# Contatore_a_relay_4bit_-_Product.net
KiCad netlist of a schematic drawn in EAGLE
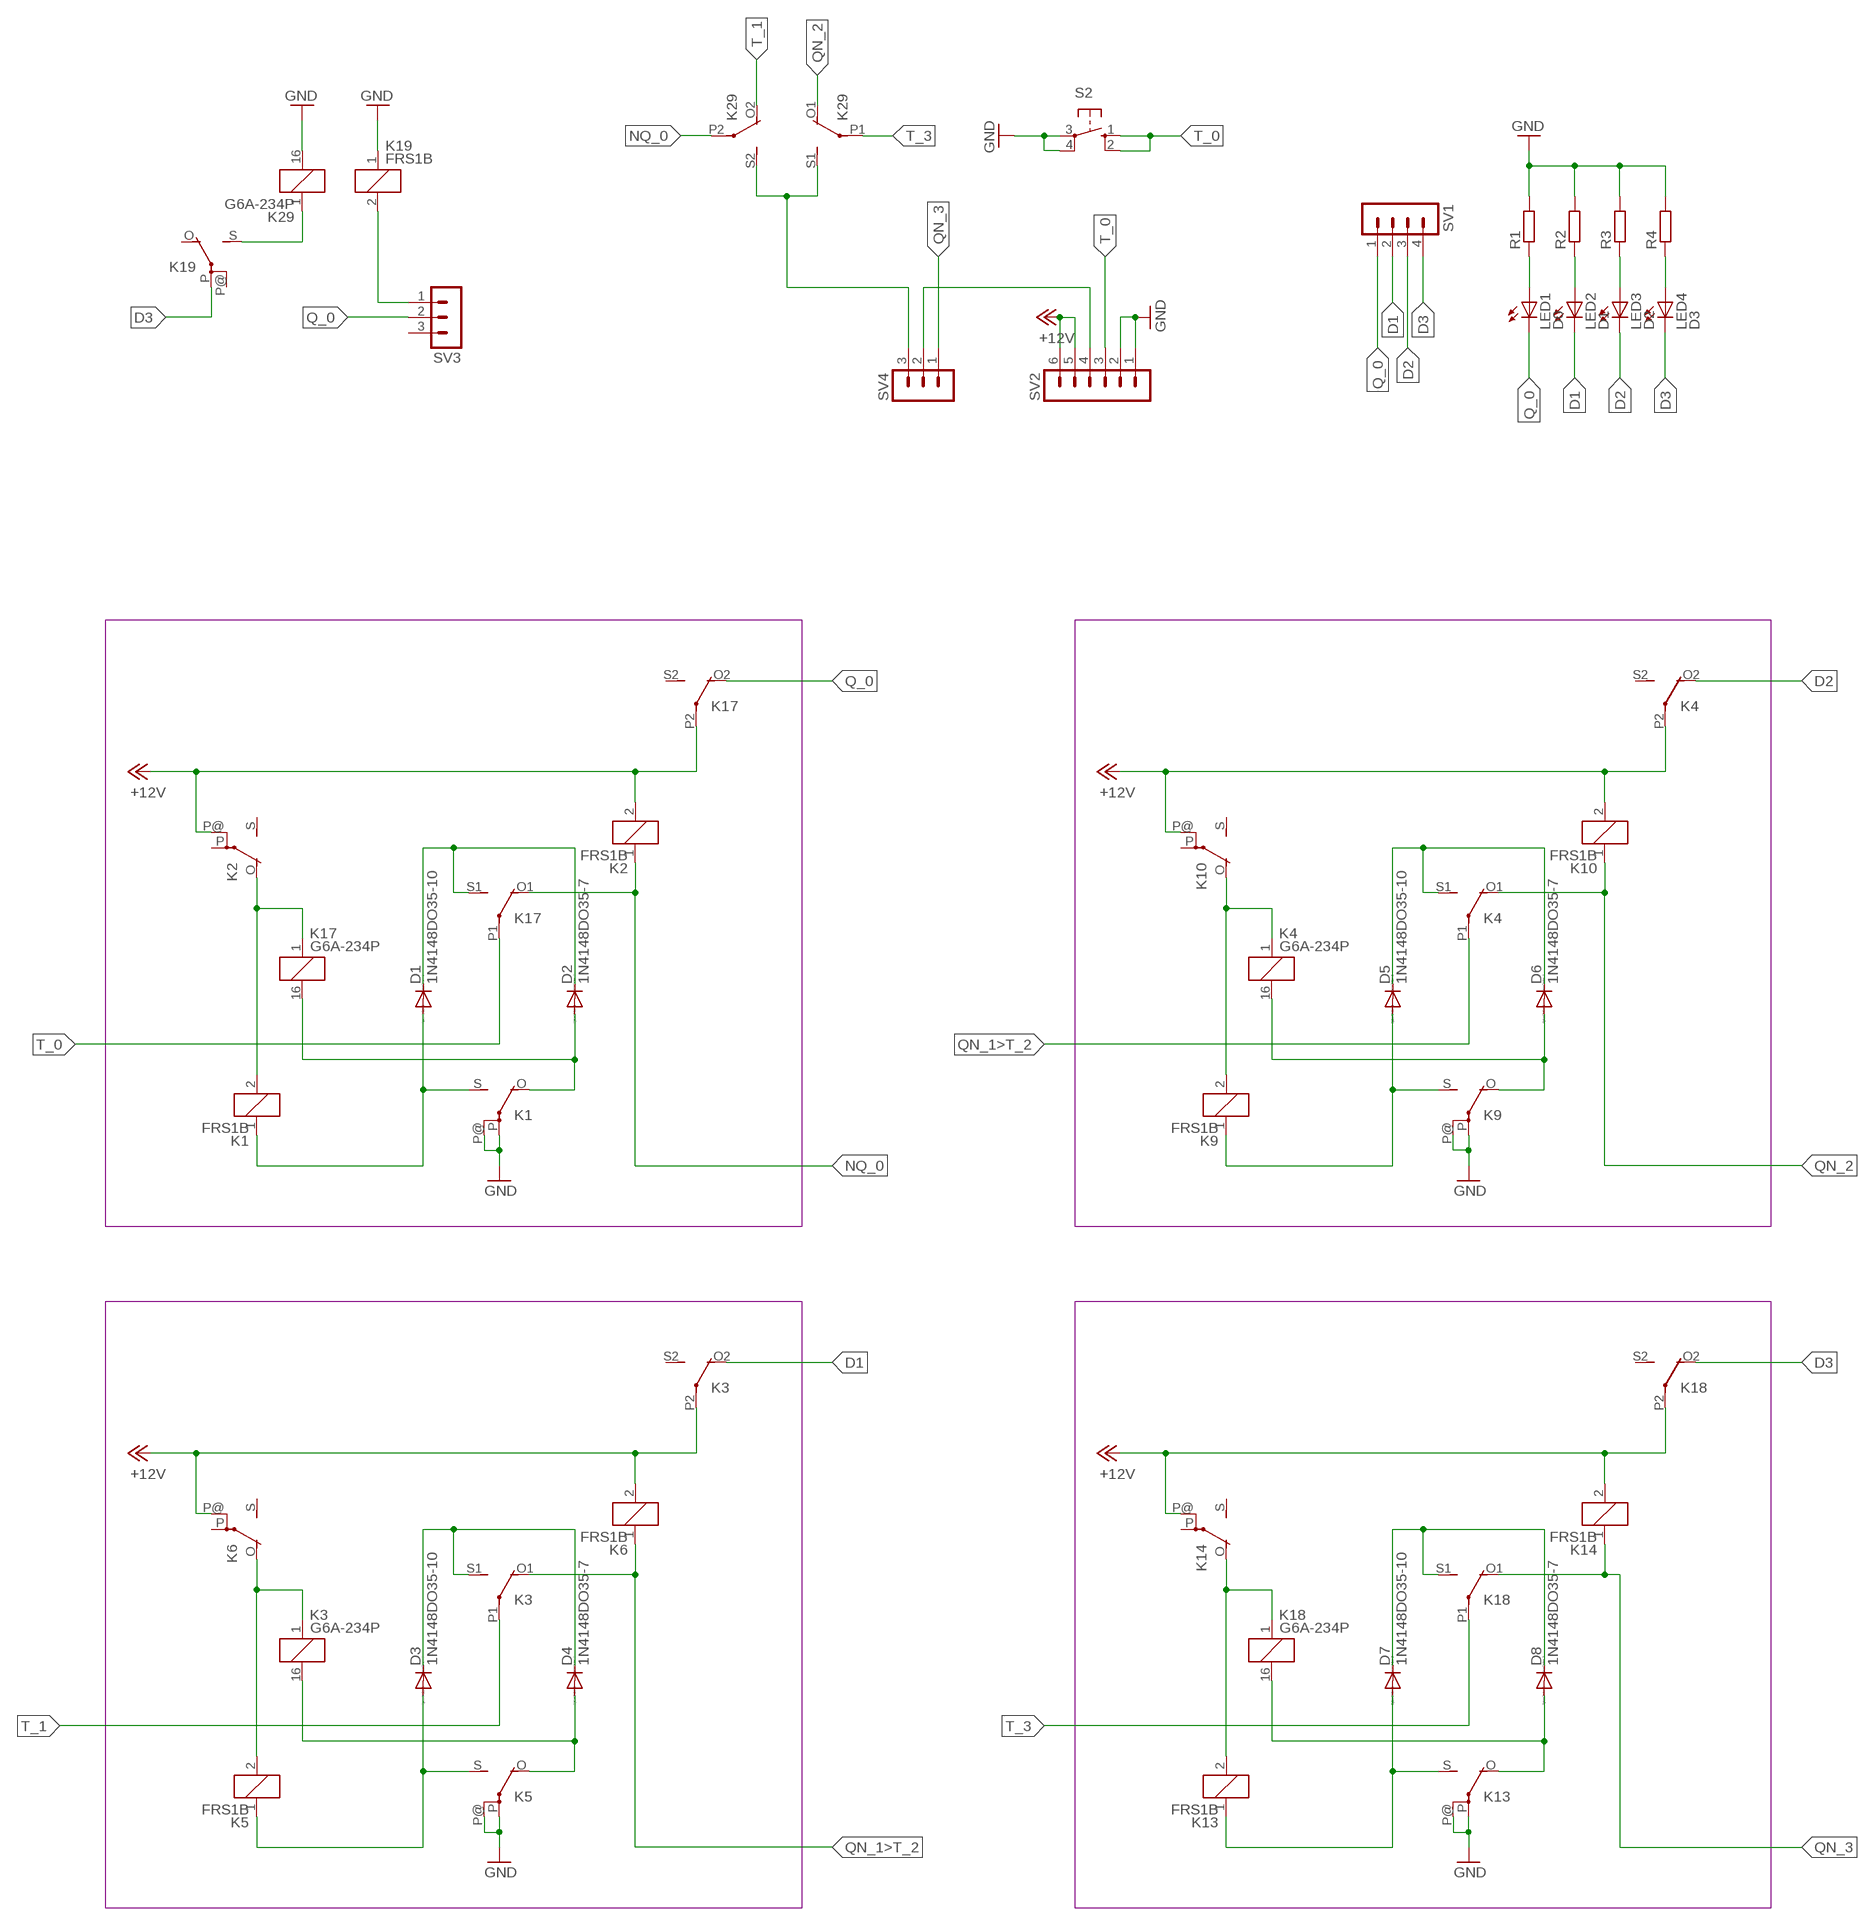
[diagram p0: schematic, sheet 1]

(export (version "E")
  (design (tool "Eeschema 10.0.6"))
  (components
    (comp (ref "D1")
      (value "1N4148DO35-10")
      (footprint "eagle-import:DO35-10")
      (libsource (lib "eagle-import") (part "1N4148DO35-10"))
    )
    (comp (ref "D2")
      (value "1N4148DO35-7")
      (footprint "eagle-import:DO35-7")
      (libsource (lib "eagle-import") (part "1N4148DO35-7"))
    )
    (comp (ref "D3")
      (value "1N4148DO35-10")
      (footprint "eagle-import:DO35-10")
      (libsource (lib "eagle-import") (part "1N4148DO35-10"))
    )
    (comp (ref "D4")
      (value "1N4148DO35-7")
      (footprint "eagle-import:DO35-7")
      (libsource (lib "eagle-import") (part "1N4148DO35-7"))
    )
    (comp (ref "D5")
      (value "1N4148DO35-10")
      (footprint "eagle-import:DO35-10")
      (libsource (lib "eagle-import") (part "1N4148DO35-10"))
    )
    (comp (ref "D6")
      (value "1N4148DO35-7")
      (footprint "eagle-import:DO35-7")
      (libsource (lib "eagle-import") (part "1N4148DO35-7"))
    )
    (comp (ref "D7")
      (value "1N4148DO35-10")
      (footprint "eagle-import:DO35-10")
      (libsource (lib "eagle-import") (part "1N4148DO35-10"))
    )
    (comp (ref "D8")
      (value "1N4148DO35-7")
      (footprint "eagle-import:DO35-7")
      (libsource (lib "eagle-import") (part "1N4148DO35-7"))
    )
    (comp (ref "K1")
      (value "FRS1B")
      (footprint "eagle-import:FRS1B")
      (libsource (lib "eagle-import") (part "FRS1B"))
    )
    (comp (ref "K2")
      (value "FRS1B")
      (footprint "eagle-import:FRS1B")
      (libsource (lib "eagle-import") (part "FRS1B"))
    )
    (comp (ref "K3")
      (value "G6A-234P")
      (footprint "eagle-import:G6A-234P")
      (libsource (lib "eagle-import") (part "G6A-234P"))
    )
    (comp (ref "K4")
      (value "G6A-234P")
      (footprint "eagle-import:G6A-234P")
      (libsource (lib "eagle-import") (part "G6A-234P"))
    )
    (comp (ref "K5")
      (value "FRS1B")
      (footprint "eagle-import:FRS1B")
      (libsource (lib "eagle-import") (part "FRS1B"))
    )
    (comp (ref "K6")
      (value "FRS1B")
      (footprint "eagle-import:FRS1B")
      (libsource (lib "eagle-import") (part "FRS1B"))
    )
    (comp (ref "K9")
      (value "FRS1B")
      (footprint "eagle-import:FRS1B")
      (libsource (lib "eagle-import") (part "FRS1B"))
    )
    (comp (ref "K10")
      (value "FRS1B")
      (footprint "eagle-import:FRS1B")
      (libsource (lib "eagle-import") (part "FRS1B"))
    )
    (comp (ref "K13")
      (value "FRS1B")
      (footprint "eagle-import:FRS1B")
      (libsource (lib "eagle-import") (part "FRS1B"))
    )
    (comp (ref "K14")
      (value "FRS1B")
      (footprint "eagle-import:FRS1B")
      (libsource (lib "eagle-import") (part "FRS1B"))
    )
    (comp (ref "K17")
      (value "G6A-234P")
      (footprint "eagle-import:G6A-234P")
      (libsource (lib "eagle-import") (part "G6A-234P"))
    )
    (comp (ref "K18")
      (value "G6A-234P")
      (footprint "eagle-import:G6A-234P")
      (libsource (lib "eagle-import") (part "G6A-234P"))
    )
    (comp (ref "K19")
      (value "FRS1B")
      (footprint "eagle-import:FRS1B")
      (libsource (lib "eagle-import") (part "FRS1B"))
    )
    (comp (ref "K29")
      (value "G6A-234P")
      (footprint "eagle-import:G6A-234P")
      (libsource (lib "eagle-import") (part "G6A-234P"))
    )
    (comp (ref "LED1")
      (value "D0")
      (footprint "eagle-import:LED3MM")
      (libsource (lib "eagle-import") (part "LED3MM"))
    )
    (comp (ref "LED2")
      (value "D1")
      (footprint "eagle-import:LED3MM")
      (libsource (lib "eagle-import") (part "LED3MM"))
    )
    (comp (ref "LED3")
      (value "D2")
      (footprint "eagle-import:LED3MM")
      (libsource (lib "eagle-import") (part "LED3MM"))
    )
    (comp (ref "LED4")
      (value "D3")
      (footprint "eagle-import:LED3MM")
      (libsource (lib "eagle-import") (part "LED3MM"))
    )
    (comp (ref "R1")
      (value "R-EU_M0805")
      (footprint "eagle-import:M0805")
      (libsource (lib "eagle-import") (part "R-EU_M0805"))
    )
    (comp (ref "R2")
      (value "R-EU_M0805")
      (footprint "eagle-import:M0805")
      (libsource (lib "eagle-import") (part "R-EU_M0805"))
    )
    (comp (ref "R3")
      (value "R-EU_M0805")
      (footprint "eagle-import:M0805")
      (libsource (lib "eagle-import") (part "R-EU_M0805"))
    )
    (comp (ref "R4")
      (value "R-EU_M0805")
      (footprint "eagle-import:M0805")
      (libsource (lib "eagle-import") (part "R-EU_M0805"))
    )
    (comp (ref "S2")
      (value "10-XX")
      (footprint "eagle-import:B3F-10XX")
      (fields (field (name "MPN") "B3F-1000"))
      (libsource (lib "eagle-import") (part "10-XX"))
    )
    (comp (ref "SV1")
      (value "MA04-1")
      (footprint "eagle-import:MA04-1")
      (libsource (lib "eagle-import") (part "MA04-1"))
    )
    (comp (ref "SV2")
      (value "MA06-1")
      (footprint "eagle-import:MA06-1")
      (libsource (lib "eagle-import") (part "MA06-1"))
    )
    (comp (ref "SV3")
      (value "MA03-1")
      (footprint "eagle-import:MA03-1")
      (libsource (lib "eagle-import") (part "MA03-1"))
    )
    (comp (ref "SV4")
      (value "MA03-1")
      (footprint "eagle-import:MA03-1")
      (libsource (lib "eagle-import") (part "MA03-1"))
    )
  )
  (nets
    (net (code "1") (name "+12V") (class "Default")
      (node (ref "K10") (pin "2") (pinfunction "2_2") (pintype "passive"))
      (node (ref "K10") (pin "P@") (pinfunction "P_P@") (pintype "passive"))
      (node (ref "K14") (pin "2") (pinfunction "2_2") (pintype "passive"))
      (node (ref "K14") (pin "P@") (pinfunction "P_P@") (pintype "passive"))
      (node (ref "K17") (pin "P2") (pinfunction "P_P2") (pintype "passive"))
      (node (ref "K18") (pin "P2") (pinfunction "P_P2") (pintype "passive"))
      (node (ref "K2") (pin "2") (pinfunction "2_2") (pintype "passive"))
      (node (ref "K2") (pin "P@") (pinfunction "P_P@") (pintype "passive"))
      (node (ref "K3") (pin "P2") (pinfunction "P_P2") (pintype "passive"))
      (node (ref "K4") (pin "P2") (pinfunction "P_P2") (pintype "passive"))
      (node (ref "K6") (pin "2") (pinfunction "2_2") (pintype "passive"))
      (node (ref "K6") (pin "P@") (pinfunction "P_P@") (pintype "passive"))
      (node (ref "SV2") (pin "5") (pinfunction "5_5") (pintype "passive"))
      (node (ref "SV2") (pin "6") (pinfunction "6_6") (pintype "passive"))
    )
    (net (code "2") (name "D1") (class "Default")
      (node (ref "K3") (pin "O2") (pinfunction "O_O2") (pintype "passive"))
      (node (ref "LED2") (pin "K") (pinfunction "C_K") (pintype "passive"))
      (node (ref "SV1") (pin "2") (pinfunction "2_2") (pintype "passive"))
    )
    (net (code "3") (name "D2") (class "Default")
      (node (ref "K4") (pin "O2") (pinfunction "O_O2") (pintype "passive"))
      (node (ref "LED3") (pin "K") (pinfunction "C_K") (pintype "passive"))
      (node (ref "SV1") (pin "3") (pinfunction "3_3") (pintype "passive"))
    )
    (net (code "4") (name "D3") (class "Default")
      (node (ref "K18") (pin "O2") (pinfunction "O_O2") (pintype "passive"))
      (node (ref "K19") (pin "P") (pinfunction "P_P") (pintype "passive"))
      (node (ref "LED4") (pin "K") (pinfunction "C_K") (pintype "passive"))
      (node (ref "SV1") (pin "4") (pinfunction "4_4") (pintype "passive"))
    )
    (net (code "5") (name "GND") (class "Default")
      (node (ref "K1") (pin "P") (pinfunction "P_P") (pintype "passive"))
      (node (ref "K1") (pin "P@") (pinfunction "P_P@") (pintype "passive"))
      (node (ref "K13") (pin "P") (pinfunction "P_P") (pintype "passive"))
      (node (ref "K13") (pin "P@") (pinfunction "P_P@") (pintype "passive"))
      (node (ref "K19") (pin "1") (pinfunction "1_1") (pintype "passive"))
      (node (ref "K29") (pin "16") (pinfunction "2_16") (pintype "passive"))
      (node (ref "K5") (pin "P") (pinfunction "P_P") (pintype "passive"))
      (node (ref "K5") (pin "P@") (pinfunction "P_P@") (pintype "passive"))
      (node (ref "K9") (pin "P") (pinfunction "P_P") (pintype "passive"))
      (node (ref "K9") (pin "P@") (pinfunction "P_P@") (pintype "passive"))
      (node (ref "R1") (pin "2") (pinfunction "2_2") (pintype "passive"))
      (node (ref "R2") (pin "2") (pinfunction "2_2") (pintype "passive"))
      (node (ref "R3") (pin "2") (pinfunction "2_2") (pintype "passive"))
      (node (ref "R4") (pin "2") (pinfunction "2_2") (pintype "passive"))
      (node (ref "S2") (pin "3") (pinfunction "P_3") (pintype "passive"))
      (node (ref "S2") (pin "4") (pinfunction "P1_4") (pintype "passive"))
      (node (ref "SV2") (pin "1") (pinfunction "1_1") (pintype "passive"))
      (node (ref "SV2") (pin "2") (pinfunction "2_2") (pintype "passive"))
    )
    (net (code "6") (name "NQ_0") (class "Default")
      (node (ref "K17") (pin "O1") (pinfunction "O_O1") (pintype "passive"))
      (node (ref "K2") (pin "1") (pinfunction "1_1") (pintype "passive"))
      (node (ref "K29") (pin "P2") (pinfunction "P_P2") (pintype "passive"))
    )
    (net (code "7") (name "Net-(D1-PadA)") (class "Default")
      (node (ref "D1") (pin "A") (pinfunction "A_A") (pintype "passive"))
      (node (ref "K1") (pin "1") (pinfunction "1_1") (pintype "passive"))
      (node (ref "K1") (pin "S") (pinfunction "S_S") (pintype "passive"))
    )
    (net (code "8") (name "Net-(D3-PadA)") (class "Default")
      (node (ref "D3") (pin "A") (pinfunction "A_A") (pintype "passive"))
      (node (ref "K5") (pin "1") (pinfunction "1_1") (pintype "passive"))
      (node (ref "K5") (pin "S") (pinfunction "S_S") (pintype "passive"))
    )
    (net (code "9") (name "Net-(D5-PadA)") (class "Default")
      (node (ref "D5") (pin "A") (pinfunction "A_A") (pintype "passive"))
      (node (ref "K9") (pin "1") (pinfunction "1_1") (pintype "passive"))
      (node (ref "K9") (pin "S") (pinfunction "S_S") (pintype "passive"))
    )
    (net (code "10") (name "Net-(D7-PadA)") (class "Default")
      (node (ref "D7") (pin "A") (pinfunction "A_A") (pintype "passive"))
      (node (ref "K13") (pin "1") (pinfunction "1_1") (pintype "passive"))
      (node (ref "K13") (pin "S") (pinfunction "S_S") (pintype "passive"))
    )
    (net (code "11") (name "Net-(K1-Pad2)") (class "Default")
      (node (ref "K1") (pin "2") (pinfunction "2_2") (pintype "passive"))
      (node (ref "K17") (pin "1") (pinfunction "1_1") (pintype "passive"))
      (node (ref "K2") (pin "O") (pinfunction "O_O") (pintype "passive"))
    )
    (net (code "12") (name "Net-(K3-Pad1)") (class "Default")
      (node (ref "K3") (pin "1") (pinfunction "1_1") (pintype "passive"))
      (node (ref "K5") (pin "2") (pinfunction "2_2") (pintype "passive"))
      (node (ref "K6") (pin "O") (pinfunction "O_O") (pintype "passive"))
    )
    (net (code "13") (name "Net-(K3A-2)") (class "Default")
      (node (ref "D4") (pin "A") (pinfunction "A_A") (pintype "passive"))
      (node (ref "K3") (pin "16") (pinfunction "2_16") (pintype "passive"))
      (node (ref "K5") (pin "O") (pinfunction "O_O") (pintype "passive"))
    )
    (net (code "14") (name "Net-(K3B-S)") (class "Default")
      (node (ref "D3") (pin "C") (pinfunction "C_C") (pintype "passive"))
      (node (ref "D4") (pin "C") (pinfunction "C_C") (pintype "passive"))
      (node (ref "K3") (pin "S1") (pinfunction "S_S1") (pintype "passive"))
    )
    (net (code "15") (name "Net-(K4A-2)") (class "Default")
      (node (ref "D6") (pin "A") (pinfunction "A_A") (pintype "passive"))
      (node (ref "K4") (pin "16") (pinfunction "2_16") (pintype "passive"))
      (node (ref "K9") (pin "O") (pinfunction "O_O") (pintype "passive"))
    )
    (net (code "16") (name "Net-(K4B-S)") (class "Default")
      (node (ref "D5") (pin "C") (pinfunction "C_C") (pintype "passive"))
      (node (ref "D6") (pin "C") (pinfunction "C_C") (pintype "passive"))
      (node (ref "K4") (pin "S1") (pinfunction "S_S1") (pintype "passive"))
    )
    (net (code "17") (name "Net-(K10-PadO)") (class "Default")
      (node (ref "K10") (pin "O") (pinfunction "O_O") (pintype "passive"))
      (node (ref "K4") (pin "1") (pinfunction "1_1") (pintype "passive"))
      (node (ref "K9") (pin "2") (pinfunction "2_2") (pintype "passive"))
    )
    (net (code "18") (name "Net-(K13-Pad2)") (class "Default")
      (node (ref "K13") (pin "2") (pinfunction "2_2") (pintype "passive"))
      (node (ref "K14") (pin "O") (pinfunction "O_O") (pintype "passive"))
      (node (ref "K18") (pin "1") (pinfunction "1_1") (pintype "passive"))
    )
    (net (code "19") (name "Net-(K17A-2)") (class "Default")
      (node (ref "D2") (pin "A") (pinfunction "A_A") (pintype "passive"))
      (node (ref "K1") (pin "O") (pinfunction "O_O") (pintype "passive"))
      (node (ref "K17") (pin "16") (pinfunction "2_16") (pintype "passive"))
    )
    (net (code "20") (name "Net-(K17B-S)") (class "Default")
      (node (ref "D1") (pin "C") (pinfunction "C_C") (pintype "passive"))
      (node (ref "D2") (pin "C") (pinfunction "C_C") (pintype "passive"))
      (node (ref "K17") (pin "S1") (pinfunction "S_S1") (pintype "passive"))
    )
    (net (code "21") (name "Net-(K18A-2)") (class "Default")
      (node (ref "D8") (pin "A") (pinfunction "A_A") (pintype "passive"))
      (node (ref "K13") (pin "O") (pinfunction "O_O") (pintype "passive"))
      (node (ref "K18") (pin "16") (pinfunction "2_16") (pintype "passive"))
    )
    (net (code "22") (name "Net-(K18B-S)") (class "Default")
      (node (ref "D7") (pin "C") (pinfunction "C_C") (pintype "passive"))
      (node (ref "D8") (pin "C") (pinfunction "C_C") (pintype "passive"))
      (node (ref "K18") (pin "S1") (pinfunction "S_S1") (pintype "passive"))
    )
    (net (code "23") (name "Net-(K19-Pad2)") (class "Default")
      (node (ref "K19") (pin "2") (pinfunction "2_2") (pintype "passive"))
      (node (ref "SV3") (pin "1") (pinfunction "1_1") (pintype "passive"))
    )
    (net (code "24") (name "Net-(K19-PadS)") (class "Default")
      (node (ref "K19") (pin "S") (pinfunction "S_S") (pintype "passive"))
      (node (ref "K29") (pin "1") (pinfunction "1_1") (pintype "passive"))
    )
    (net (code "25") (name "Net-(K29B-S)") (class "Default")
      (node (ref "K29") (pin "S1") (pinfunction "S_S1") (pintype "passive"))
      (node (ref "K29") (pin "S2") (pinfunction "S_S2") (pintype "passive"))
      (node (ref "SV4") (pin "3") (pinfunction "3_3") (pintype "passive"))
    )
    (net (code "26") (name "Net-(LED1-PadA)") (class "Default")
      (node (ref "LED1") (pin "A") (pinfunction "A_A") (pintype "passive"))
      (node (ref "R1") (pin "1") (pinfunction "1_1") (pintype "passive"))
    )
    (net (code "27") (name "Net-(LED2-PadA)") (class "Default")
      (node (ref "LED2") (pin "A") (pinfunction "A_A") (pintype "passive"))
      (node (ref "R2") (pin "1") (pinfunction "1_1") (pintype "passive"))
    )
    (net (code "28") (name "Net-(LED3-PadA)") (class "Default")
      (node (ref "LED3") (pin "A") (pinfunction "A_A") (pintype "passive"))
      (node (ref "R3") (pin "1") (pinfunction "1_1") (pintype "passive"))
    )
    (net (code "29") (name "Net-(LED4-PadA)") (class "Default")
      (node (ref "LED4") (pin "A") (pinfunction "A_A") (pintype "passive"))
      (node (ref "R4") (pin "1") (pinfunction "1_1") (pintype "passive"))
    )
    (net (code "30") (name "Net-(SV2-Pad4)") (class "Default")
      (node (ref "SV2") (pin "4") (pinfunction "4_4") (pintype "passive"))
      (node (ref "SV4") (pin "2") (pinfunction "2_2") (pintype "passive"))
    )
    (net (code "31") (name "QN_1>T_2") (class "Default")
      (node (ref "K3") (pin "O1") (pinfunction "O_O1") (pintype "passive"))
      (node (ref "K4") (pin "P1") (pinfunction "P_P1") (pintype "passive"))
      (node (ref "K6") (pin "1") (pinfunction "1_1") (pintype "passive"))
    )
    (net (code "32") (name "QN_2") (class "Default")
      (node (ref "K10") (pin "1") (pinfunction "1_1") (pintype "passive"))
      (node (ref "K29") (pin "O1") (pinfunction "O_O1") (pintype "passive"))
      (node (ref "K4") (pin "O1") (pinfunction "O_O1") (pintype "passive"))
    )
    (net (code "33") (name "QN_3") (class "Default")
      (node (ref "K14") (pin "1") (pinfunction "1_1") (pintype "passive"))
      (node (ref "K18") (pin "O1") (pinfunction "O_O1") (pintype "passive"))
      (node (ref "SV4") (pin "1") (pinfunction "1_1") (pintype "passive"))
    )
    (net (code "34") (name "Q_0") (class "Default")
      (node (ref "K17") (pin "O2") (pinfunction "O_O2") (pintype "passive"))
      (node (ref "LED1") (pin "K") (pinfunction "C_K") (pintype "passive"))
      (node (ref "SV1") (pin "1") (pinfunction "1_1") (pintype "passive"))
      (node (ref "SV3") (pin "2") (pinfunction "2_2") (pintype "passive"))
    )
    (net (code "35") (name "T_0") (class "Default")
      (node (ref "K17") (pin "P1") (pinfunction "P_P1") (pintype "passive"))
      (node (ref "S2") (pin "1") (pinfunction "S_1") (pintype "passive"))
      (node (ref "S2") (pin "2") (pinfunction "S1_2") (pintype "passive"))
      (node (ref "SV2") (pin "3") (pinfunction "3_3") (pintype "passive"))
    )
    (net (code "36") (name "T_1") (class "Default")
      (node (ref "K29") (pin "O2") (pinfunction "O_O2") (pintype "passive"))
      (node (ref "K3") (pin "P1") (pinfunction "P_P1") (pintype "passive"))
    )
    (net (code "37") (name "T_3") (class "Default")
      (node (ref "K18") (pin "P1") (pinfunction "P_P1") (pintype "passive"))
      (node (ref "K29") (pin "P1") (pinfunction "P_P1") (pintype "passive"))
    )
    (net (code "38") (name "unconnected-(K2-PadP)") (class "Default")
      (node (ref "K2") (pin "P") (pinfunction "P_P") (pintype "passive"))
    )
    (net (code "39") (name "unconnected-(K2-PadS)") (class "Default")
      (node (ref "K2") (pin "S") (pinfunction "S_S") (pintype "passive"))
    )
    (net (code "40") (name "unconnected-(K3C-S-PadS2)") (class "Default")
      (node (ref "K3") (pin "S2") (pinfunction "S_S2") (pintype "passive"))
    )
    (net (code "41") (name "unconnected-(K4C-S-PadS2)") (class "Default")
      (node (ref "K4") (pin "S2") (pinfunction "S_S2") (pintype "passive"))
    )
    (net (code "42") (name "unconnected-(K6-PadP)") (class "Default")
      (node (ref "K6") (pin "P") (pinfunction "P_P") (pintype "passive"))
    )
    (net (code "43") (name "unconnected-(K6-PadS)") (class "Default")
      (node (ref "K6") (pin "S") (pinfunction "S_S") (pintype "passive"))
    )
    (net (code "44") (name "unconnected-(K10-PadP)") (class "Default")
      (node (ref "K10") (pin "P") (pinfunction "P_P") (pintype "passive"))
    )
    (net (code "45") (name "unconnected-(K10-PadS)") (class "Default")
      (node (ref "K10") (pin "S") (pinfunction "S_S") (pintype "passive"))
    )
    (net (code "46") (name "unconnected-(K14-PadP)") (class "Default")
      (node (ref "K14") (pin "P") (pinfunction "P_P") (pintype "passive"))
    )
    (net (code "47") (name "unconnected-(K14-PadS)") (class "Default")
      (node (ref "K14") (pin "S") (pinfunction "S_S") (pintype "passive"))
    )
    (net (code "48") (name "unconnected-(K17C-S-PadS2)") (class "Default")
      (node (ref "K17") (pin "S2") (pinfunction "S_S2") (pintype "passive"))
    )
    (net (code "49") (name "unconnected-(K18C-S-PadS2)") (class "Default")
      (node (ref "K18") (pin "S2") (pinfunction "S_S2") (pintype "passive"))
    )
    (net (code "50") (name "unconnected-(K19-PadO)") (class "Default")
      (node (ref "K19") (pin "O") (pinfunction "O_O") (pintype "passive"))
    )
    (net (code "51") (name "unconnected-(K19B-P-PadP@)") (class "Default")
      (node (ref "K19") (pin "P@") (pinfunction "P_P@") (pintype "passive"))
    )
    (net (code "52") (name "unconnected-(SV3-Pad3)") (class "Default")
      (node (ref "SV3") (pin "3") (pinfunction "3_3") (pintype "passive"))
    )
  )
)
